# Power___Mechanical.net
KiCad netlist of a schematic drawn in Altium Designer
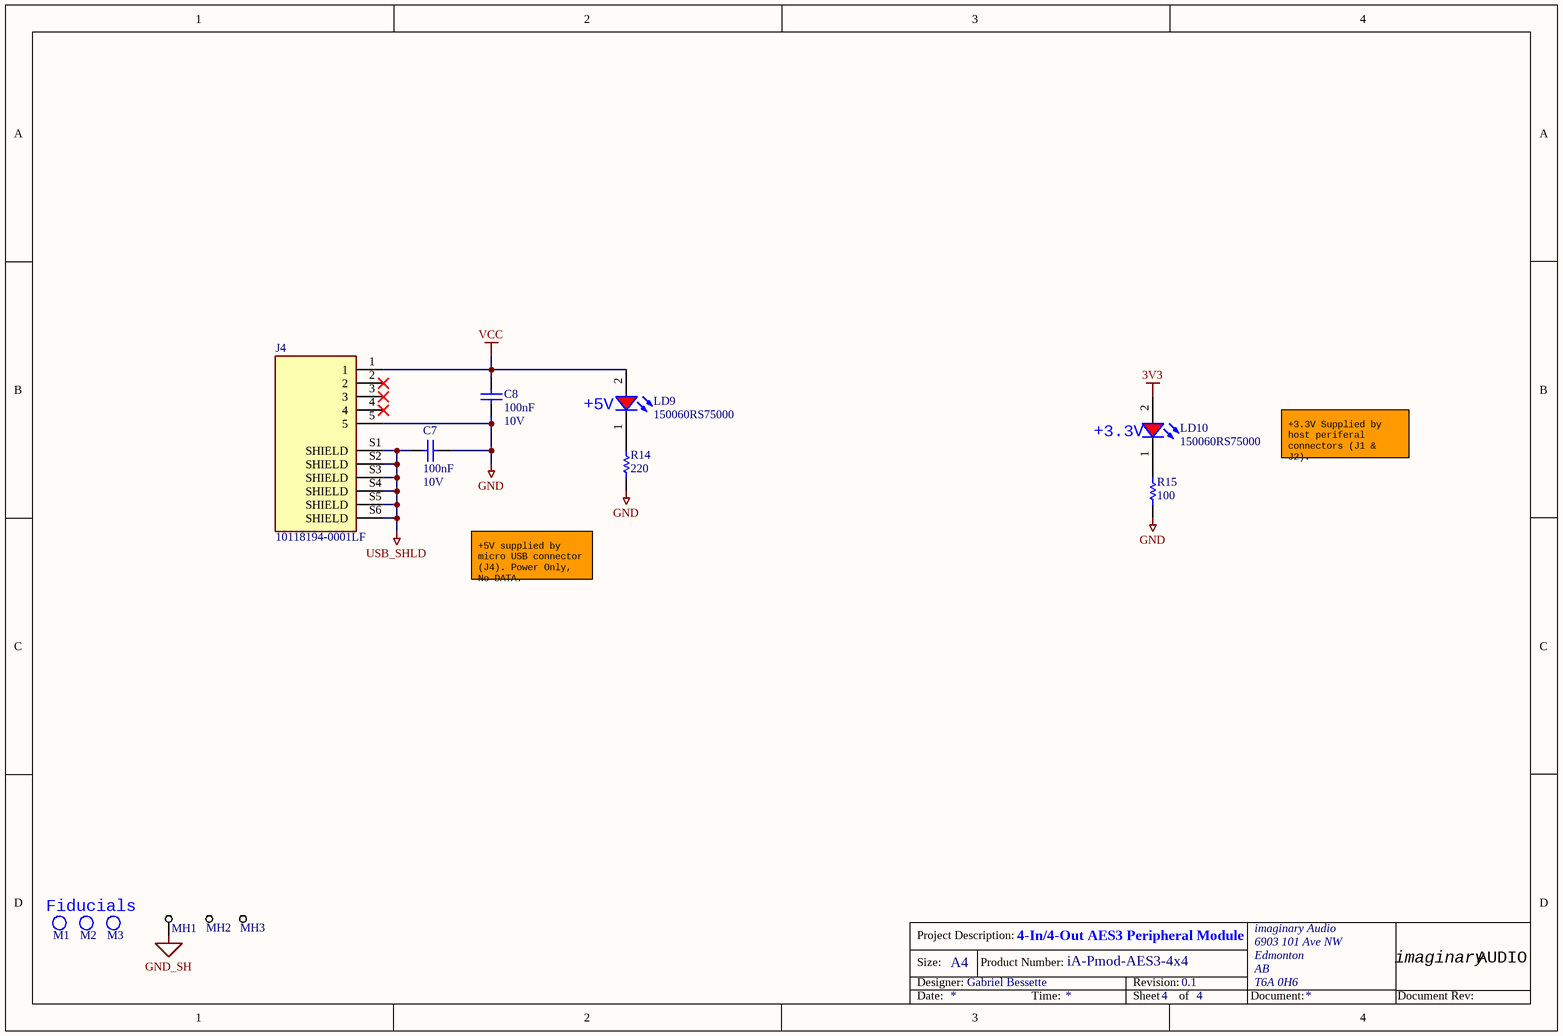
[diagram p0: Power_&_Mechanical.SchDoc]

(export (version "E")
  (design (tool "Eeschema 10.0.6"))
  (components
    (comp (ref "C7")
      (value "100nF")
      (footprint "CAPC0603(1608)100_N")
      (fields
        (field (name "MANUFACTURER") "KEMET")
        (field (name "MANUFACTURER PART NUMBER") "C0603C104K8RACTU")
        (field (name "TOLERANCE") "10%")
        (field (name "VOLTAGE") "10V")
      )
      (libsource (lib "iA-IntLib") (part "CAP"))
    )
    (comp (ref "C8")
      (value "100nF")
      (footprint "CAPC0603(1608)100_N")
      (fields
        (field (name "MANUFACTURER") "KEMET")
        (field (name "MANUFACTURER PART NUMBER") "C0603C104K8RACTU")
        (field (name "TOLERANCE") "10%")
        (field (name "VOLTAGE") "10V")
      )
      (libsource (lib "iA-IntLib") (part "CAP"))
    )
    (comp (ref "J4")
      (value "10118194-0001LF")
      (footprint "10118194-0001LF")
      (description "CONN, USB MICRO B RECPT SMT R/A")
      (fields
        (field (name "MF") "Amphenol ICC")
        (field (name "MANUFACTURER") "Amphenol FCI")
        (field (name "MANUFACTURER PART NUMBER") "10118194-0001LF")
      )
      (libsource (lib "iA-IntLib") (part "10118194-0001LF"))
    )
    (comp (ref "LD9")
      (value "150060RS75000")
      (footprint "WL-SMCW_0603_H=0.7mm")
      (description "LED, Red, 625 nm, 2 V, 30 mA, 250 mcd RoHS Compliant")
      (fields (field (name "MANUFACTURER") "Wurth Electronics"))
      (libsource (lib "iA-IntLib") (part "150060RS75000"))
    )
    (comp (ref "LD10")
      (value "150060RS75000")
      (footprint "WL-SMCW_0603_H=0.7mm")
      (description "LED, Red, 625 nm, 2 V, 30 mA, 250 mcd RoHS Compliant")
      (fields (field (name "MANUFACTURER") "Wurth Electronics"))
      (libsource (lib "iA-IntLib") (part "150060RS75000"))
    )
    (comp (ref "M1")
      (value "FIDUCIAL Marker, 1mm-2mm, 2-Layers + Keepout")
      (footprint "FIDUCIAL_D-2D_2-Layer")
      (libsource (lib "iA-IntLib") (part "FIDUCIAL_D-2D_2L"))
    )
    (comp (ref "M2")
      (value "FIDUCIAL Marker, 1mm-2mm, 2-Layers + Keepout")
      (footprint "FIDUCIAL_D-2D_2-Layer")
      (libsource (lib "iA-IntLib") (part "FIDUCIAL_D-2D_2L"))
    )
    (comp (ref "M3")
      (value "FIDUCIAL Marker, 1mm-2mm, 2-Layers + Keepout")
      (footprint "FIDUCIAL_D-2D_2-Layer")
      (libsource (lib "iA-IntLib") (part "FIDUCIAL_D-2D_2L"))
    )
    (comp (ref "MH1")
      (value "*")
      (footprint "MH_GND_M3")
      (description "Mounting Hole, Grounded, Generic")
      (libsource (lib "iA-IntLib") (part "MountingHole_GND"))
    )
    (comp (ref "MH2")
      (value "*")
      (footprint "MH_M3_NPTH")
      (description "Mounting Hole, Generic")
      (libsource (lib "iA-IntLib") (part "MountingHole"))
    )
    (comp (ref "MH3")
      (value "*")
      (footprint "MH_M3_NPTH")
      (description "Mounting Hole, Generic")
      (libsource (lib "iA-IntLib") (part "MountingHole"))
    )
    (comp (ref "R14")
      (value "220")
      (footprint "RESC1608X55X30NL15T15")
      (description "Resistor Thick Film 0603 220 Ohm 1% 1/10W 100ppm/C Molded SMD Punched Carrier T/R")
      (fields (field (name "MANUFACTURER PART NUMBER") "ERJ3EKF2200V") (field (name "TOLERANCE") "1%"))
      (libsource (lib "iA-IntLib") (part "RES"))
    )
    (comp (ref "R15")
      (value "100")
      (footprint "RESC1608X55X30NL15T15")
      (description "RES SMD 100 OHM 1% 1/10W 0603")
      (fields (field (name "MANUFACTURER PART NUMBER") "ERJ3EKF1000V") (field (name "TOLERANCE") "1%"))
      (libsource (lib "iA-IntLib") (part "RES"))
    )
  )
  (nets
    (net (code "1") (name "3V3") (class "Default")
      (node (ref "LD10") (pin "2") (pinfunction "A_2") (pintype "passive"))
    )
    (net (code "2") (name "GND") (class "Default")
      (node (ref "C7") (pin "1") (pinfunction "1_1") (pintype "passive"))
      (node (ref "C8") (pin "1") (pinfunction "1_1") (pintype "passive"))
      (node (ref "J4") (pin "5") (pinfunction "5_5") (pintype "passive"))
      (node (ref "R14") (pin "1") (pinfunction "1_1") (pintype "passive"))
      (node (ref "R15") (pin "1") (pinfunction "1_1") (pintype "passive"))
    )
    (net (code "3") (name "GND_SH") (class "Default") (node (ref "MH1") (pin "1") (pintype "passive")))
    (net (code "4") (name "Net-(LD9-K)") (class "Default")
      (node (ref "LD9") (pin "1") (pinfunction "K_1") (pintype "passive"))
      (node (ref "R14") (pin "2") (pinfunction "2_2") (pintype "passive"))
    )
    (net (code "5") (name "Net-(LD10-K)") (class "Default")
      (node (ref "LD10") (pin "1") (pinfunction "K_1") (pintype "passive"))
      (node (ref "R15") (pin "2") (pinfunction "2_2") (pintype "passive"))
    )
    (net (code "6") (name "USB_SHLD") (class "Default")
      (node (ref "C7") (pin "2") (pinfunction "2_2") (pintype "passive"))
      (node (ref "J4") (pin "S1") (pinfunction "SHIELD_S1") (pintype "passive"))
      (node (ref "J4") (pin "S2") (pinfunction "SHIELD_S2") (pintype "passive"))
      (node (ref "J4") (pin "S3") (pinfunction "SHIELD_S3") (pintype "passive"))
      (node (ref "J4") (pin "S4") (pinfunction "SHIELD_S4") (pintype "passive"))
      (node (ref "J4") (pin "S5") (pinfunction "SHIELD_S5") (pintype "passive"))
      (node (ref "J4") (pin "S6") (pinfunction "SHIELD_S6") (pintype "passive"))
    )
    (net (code "7") (name "VCC") (class "Default")
      (node (ref "C8") (pin "2") (pinfunction "2_2") (pintype "passive"))
      (node (ref "J4") (pin "1") (pinfunction "1_1") (pintype "passive"))
      (node (ref "LD9") (pin "2") (pinfunction "A_2") (pintype "passive"))
    )
    (net (code "8") (name "unconnected-(J4-Pad2)") (class "Default")
      (node (ref "J4") (pin "2") (pinfunction "2_2") (pintype "passive+no_connect"))
    )
    (net (code "9") (name "unconnected-(J4-Pad3)") (class "Default")
      (node (ref "J4") (pin "3") (pinfunction "3_3") (pintype "passive+no_connect"))
    )
    (net (code "10") (name "unconnected-(J4-Pad4)") (class "Default")
      (node (ref "J4") (pin "4") (pinfunction "4_4") (pintype "passive+no_connect"))
    )
  )
)
